# TaaraNodeMini.net
KiCad netlist of a schematic drawn in EAGLE
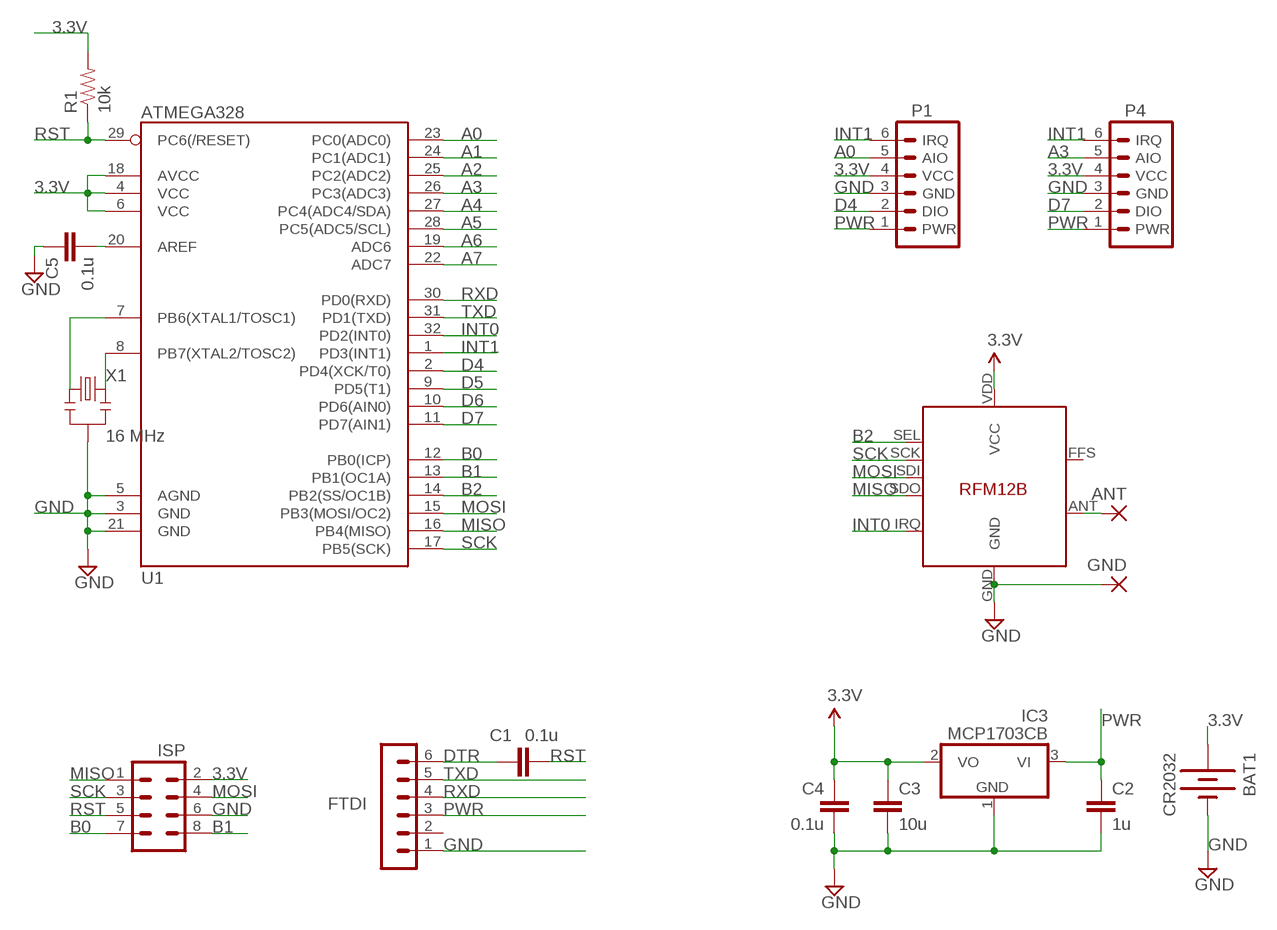
[diagram p0: schematic, sheet 1]

(export (version "E")
  (design (tool "Eeschema 10.0.6"))
  (components
    (comp (ref "ANT")
      (value "1,6/0,8")
      (footprint "eagle-import:1,6_0,8")
      (libsource (lib "eagle-import") (part "1,6/0,8"))
    )
    (comp (ref "BAT1")
      (value "CR2032")
      (footprint "eagle-import:BATTCOM_20MM_PTH")
      (libsource (lib "eagle-import") (part "BATTERY20PTH"))
    )
    (comp (ref "C1")
      (value "0.1u")
      (footprint "eagle-import:0603-CAP")
      (libsource (lib "eagle-import") (part "CAP0603-CAP"))
    )
    (comp (ref "C2")
      (value "1u")
      (footprint "eagle-import:0603-CAP")
      (libsource (lib "eagle-import") (part "CAP0603-CAP"))
    )
    (comp (ref "C3")
      (value "10u")
      (footprint "eagle-import:0805")
      (libsource (lib "eagle-import") (part "CAP0805"))
    )
    (comp (ref "C4")
      (value "0.1u")
      (footprint "eagle-import:0603-CAP")
      (libsource (lib "eagle-import") (part "CAP0603-CAP"))
    )
    (comp (ref "C5")
      (value "0.1u")
      (footprint "eagle-import:0603-CAP")
      (libsource (lib "eagle-import") (part "CAP0603-CAP"))
    )
    (comp (ref "FTDI")
      (value "FTDI")
      (footprint "eagle-import:MA06-1")
      (libsource (lib "eagle-import") (part "MA06-1"))
    )
    (comp (ref "GND")
      (value "1,6/0,8")
      (footprint "eagle-import:1,6_0,8")
      (libsource (lib "eagle-import") (part "1,6/0,8"))
    )
    (comp (ref "IC3")
      (value "MCP1703CB")
      (footprint "eagle-import:SOT23")
      (libsource (lib "eagle-import") (part "MCP1703CB"))
    )
    (comp (ref "P1")
      (value "JEEPORT")
      (footprint "eagle-import:1X06_FEMALE_LOCK.010")
      (libsource (lib "eagle-import") (part "JEEPORT-FEMALE"))
    )
    (comp (ref "P4")
      (value "JEEPORT")
      (footprint "eagle-import:1X06_FEMALE_LOCK.010")
      (libsource (lib "eagle-import") (part "JEEPORT-FEMALE"))
    )
    (comp (ref "R1")
      (value "10k")
      (footprint "eagle-import:0603-RES")
      (libsource (lib "eagle-import") (part "RESISTOR0603-RES"))
    )
    (comp (ref "SV7")
      (value "ISP")
      (footprint "eagle-import:MA04-2")
      (libsource (lib "eagle-import") (part "MA04-2"))
    )
    (comp (ref "U$1")
      (value "RFM12B")
      (footprint "eagle-import:RFM12B")
      (libsource (lib "eagle-import") (part "RFM12B"))
    )
    (comp (ref "U1")
      (value "ATMEGA328")
      (footprint "eagle-import:TQFP32-08")
      (libsource (lib "eagle-import") (part "ATMEGA168"))
    )
    (comp (ref "X1")
      (value "16 MHz")
      (footprint "eagle-import:RESONATOR-SMD")
      (libsource (lib "eagle-import") (part "RESONATORSMD"))
    )
  )
  (nets
    (net (code "1") (name "/A0") (class "Default")
      (node (ref "P1") (pin "5") (pinfunction "AIO_5") (pintype "bidirectional"))
      (node (ref "U1") (pin "23") (pinfunction "PC0(ADC0)_23") (pintype "bidirectional"))
    )
    (net (code "2") (name "/A1") (class "Default")
      (node (ref "U1") (pin "24") (pinfunction "PC1(ADC1)_24") (pintype "bidirectional"))
    )
    (net (code "3") (name "/A2") (class "Default")
      (node (ref "U1") (pin "25") (pinfunction "PC2(ADC2)_25") (pintype "bidirectional"))
    )
    (net (code "4") (name "/A3") (class "Default")
      (node (ref "P4") (pin "5") (pinfunction "AIO_5") (pintype "bidirectional"))
      (node (ref "U1") (pin "26") (pinfunction "PC3(ADC3)_26") (pintype "bidirectional"))
    )
    (net (code "5") (name "/A4") (class "Default")
      (node (ref "U1") (pin "27") (pinfunction "PC4(ADC4/SDA)_27") (pintype "bidirectional"))
    )
    (net (code "6") (name "/A5") (class "Default")
      (node (ref "U1") (pin "28") (pinfunction "PC5(ADC5/SCL)_28") (pintype "bidirectional"))
    )
    (net (code "7") (name "/A6") (class "Default")
      (node (ref "U1") (pin "19") (pinfunction "ADC6_19") (pintype "bidirectional"))
    )
    (net (code "8") (name "/A7") (class "Default")
      (node (ref "U1") (pin "22") (pinfunction "ADC7_22") (pintype "bidirectional"))
    )
    (net (code "9") (name "/B0") (class "Default")
      (node (ref "SV7") (pin "7") (pinfunction "7_7") (pintype "passive"))
      (node (ref "U1") (pin "12") (pinfunction "PB0(ICP)_12") (pintype "bidirectional"))
    )
    (net (code "10") (name "/B1") (class "Default")
      (node (ref "SV7") (pin "8") (pinfunction "8_8") (pintype "passive"))
      (node (ref "U1") (pin "13") (pinfunction "PB1(OC1A)_13") (pintype "bidirectional"))
    )
    (net (code "11") (name "/B2") (class "Default")
      (node (ref "U$1") (pin "SEL") (pinfunction "SEL_SEL") (pintype "input"))
      (node (ref "U1") (pin "14") (pinfunction "PB2(SS/OC1B)_14") (pintype "bidirectional"))
    )
    (net (code "12") (name "/D4") (class "Default")
      (node (ref "P1") (pin "2") (pinfunction "DIO_2") (pintype "bidirectional"))
      (node (ref "U1") (pin "2") (pinfunction "PD4(XCK/T0)_2") (pintype "bidirectional"))
    )
    (net (code "13") (name "/D5") (class "Default")
      (node (ref "U1") (pin "9") (pinfunction "PD5(T1)_9") (pintype "bidirectional"))
    )
    (net (code "14") (name "/D6") (class "Default")
      (node (ref "U1") (pin "10") (pinfunction "PD6(AIN0)_10") (pintype "bidirectional"))
    )
    (net (code "15") (name "/D7") (class "Default")
      (node (ref "P4") (pin "2") (pinfunction "DIO_2") (pintype "bidirectional"))
      (node (ref "U1") (pin "11") (pinfunction "PD7(AIN1)_11") (pintype "bidirectional"))
    )
    (net (code "16") (name "/DTR") (class "Default")
      (node (ref "C1") (pin "2") (pinfunction "2_2") (pintype "passive"))
      (node (ref "FTDI") (pin "6") (pinfunction "6_6") (pintype "passive"))
    )
    (net (code "17") (name "/INT0") (class "Default")
      (node (ref "U$1") (pin "IRQ") (pinfunction "IRQ_IRQ") (pintype "open_collector"))
      (node (ref "U1") (pin "32") (pinfunction "PD2(INT0)_32") (pintype "bidirectional"))
    )
    (net (code "18") (name "/INT1") (class "Default")
      (node (ref "P1") (pin "6") (pinfunction "IRQ_6") (pintype "bidirectional"))
      (node (ref "P4") (pin "6") (pinfunction "IRQ_6") (pintype "bidirectional"))
      (node (ref "U1") (pin "1") (pinfunction "PD3(INT1)_1") (pintype "bidirectional"))
    )
    (net (code "19") (name "/MISO") (class "Default")
      (node (ref "SV7") (pin "1") (pinfunction "1_1") (pintype "passive"))
      (node (ref "U$1") (pin "SDO") (pinfunction "SDO_SDO") (pintype "output"))
      (node (ref "U1") (pin "16") (pinfunction "PB4(MISO)_16") (pintype "bidirectional"))
    )
    (net (code "20") (name "/MOSI") (class "Default")
      (node (ref "SV7") (pin "4") (pinfunction "4_4") (pintype "passive"))
      (node (ref "U$1") (pin "SDI") (pinfunction "SDI_SDI") (pintype "input"))
      (node (ref "U1") (pin "15") (pinfunction "PB3(MOSI/OC2)_15") (pintype "bidirectional"))
    )
    (net (code "21") (name "/PWR") (class "Default")
      (node (ref "C2") (pin "1") (pinfunction "1_1") (pintype "passive"))
      (node (ref "FTDI") (pin "3") (pinfunction "3_3") (pintype "passive"))
      (node (ref "IC3") (pin "3") (pinfunction "VI_3") (pintype "input"))
      (node (ref "P1") (pin "1") (pinfunction "PWR_1") (pintype "power_in"))
      (node (ref "P4") (pin "1") (pinfunction "PWR_1") (pintype "power_in"))
    )
    (net (code "22") (name "/RST") (class "Default")
      (node (ref "C1") (pin "1") (pinfunction "1_1") (pintype "passive"))
      (node (ref "R1") (pin "1") (pinfunction "1_1") (pintype "passive"))
      (node (ref "SV7") (pin "5") (pinfunction "5_5") (pintype "passive"))
      (node (ref "U1") (pin "29") (pinfunction "PC6(/RESET)_29") (pintype "bidirectional"))
    )
    (net (code "23") (name "/RXD") (class "Default")
      (node (ref "FTDI") (pin "4") (pinfunction "4_4") (pintype "passive"))
      (node (ref "U1") (pin "30") (pinfunction "PD0(RXD)_30") (pintype "bidirectional"))
    )
    (net (code "24") (name "/SCK") (class "Default")
      (node (ref "SV7") (pin "3") (pinfunction "3_3") (pintype "passive"))
      (node (ref "U$1") (pin "SCK") (pinfunction "SCK_SCK") (pintype "input"))
      (node (ref "U1") (pin "17") (pinfunction "PB5(SCK)_17") (pintype "bidirectional"))
    )
    (net (code "25") (name "/TXD") (class "Default")
      (node (ref "FTDI") (pin "5") (pinfunction "5_5") (pintype "passive"))
      (node (ref "U1") (pin "31") (pinfunction "PD1(TXD)_31") (pintype "bidirectional"))
    )
    (net (code "26") (name "3.3V") (class "Default")
      (node (ref "BAT1") (pin "1") (pinfunction "+_1") (pintype "power_in"))
      (node (ref "C3") (pin "1") (pinfunction "1_1") (pintype "passive"))
      (node (ref "C4") (pin "1") (pinfunction "1_1") (pintype "passive"))
      (node (ref "IC3") (pin "2") (pinfunction "VO_2") (pintype "passive"))
      (node (ref "P1") (pin "4") (pinfunction "VCC_4") (pintype "power_in"))
      (node (ref "P4") (pin "4") (pinfunction "VCC_4") (pintype "power_in"))
      (node (ref "R1") (pin "2") (pinfunction "2_2") (pintype "passive"))
      (node (ref "SV7") (pin "2") (pinfunction "2_2") (pintype "passive"))
      (node (ref "U$1") (pin "VDD") (pinfunction "VCC_VDD") (pintype "power_in"))
      (node (ref "U1") (pin "18") (pinfunction "AVCC_18") (pintype "bidirectional"))
      (node (ref "U1") (pin "4") (pinfunction "VCC_4") (pintype "bidirectional"))
      (node (ref "U1") (pin "6") (pinfunction "VCC_6") (pintype "bidirectional"))
    )
    (net (code "27") (name "GND") (class "Default")
      (node (ref "BAT1") (pin "2") (pinfunction "-_2") (pintype "power_in"))
      (node (ref "C2") (pin "2") (pinfunction "2_2") (pintype "passive"))
      (node (ref "C3") (pin "2") (pinfunction "2_2") (pintype "passive"))
      (node (ref "C4") (pin "2") (pinfunction "2_2") (pintype "passive"))
      (node (ref "C5") (pin "1") (pinfunction "1_1") (pintype "passive"))
      (node (ref "FTDI") (pin "1") (pinfunction "1_1") (pintype "passive"))
      (node (ref "GND") (pin "1") (pinfunction "P_1") (pintype "passive"))
      (node (ref "IC3") (pin "1") (pinfunction "GND_1") (pintype "passive"))
      (node (ref "P1") (pin "3") (pinfunction "GND_3") (pintype "power_in"))
      (node (ref "P4") (pin "3") (pinfunction "GND_3") (pintype "power_in"))
      (node (ref "SV7") (pin "6") (pinfunction "6_6") (pintype "passive"))
      (node (ref "U$1") (pin "GND") (pinfunction "GND_GND") (pintype "power_in"))
      (node (ref "U1") (pin "21") (pinfunction "GND_21") (pintype "bidirectional"))
      (node (ref "U1") (pin "3") (pinfunction "GND_3") (pintype "bidirectional"))
      (node (ref "U1") (pin "5") (pinfunction "AGND_5") (pintype "bidirectional"))
      (node (ref "X1") (pin "2") (pinfunction "2_2") (pintype "passive"))
    )
    (net (code "28") (name "Net-(ANT-P)") (class "Default")
      (node (ref "ANT") (pin "1") (pinfunction "P_1") (pintype "passive"))
      (node (ref "U$1") (pin "ANT") (pinfunction "ANT_ANT") (pintype "passive"))
    )
    (net (code "29") (name "Net-(U1-AREF)") (class "Default")
      (node (ref "C5") (pin "2") (pinfunction "2_2") (pintype "passive"))
      (node (ref "U1") (pin "20") (pinfunction "AREF_20") (pintype "bidirectional"))
    )
    (net (code "30") (name "Net-(U1-PB6(XTAL1{slash}TOSC1))") (class "Default")
      (node (ref "U1") (pin "7") (pinfunction "PB6(XTAL1/TOSC1)_7") (pintype "bidirectional"))
      (node (ref "X1") (pin "1") (pinfunction "1_1") (pintype "passive"))
    )
    (net (code "31") (name "Net-(U1-PB7(XTAL2{slash}TOSC2))") (class "Default")
      (node (ref "U1") (pin "8") (pinfunction "PB7(XTAL2/TOSC2)_8") (pintype "bidirectional"))
      (node (ref "X1") (pin "3") (pinfunction "3_3") (pintype "passive"))
    )
    (net (code "32") (name "unconnected-(FTDI-Pad2)") (class "Default")
      (node (ref "FTDI") (pin "2") (pinfunction "2_2") (pintype "passive"))
    )
    (net (code "33") (name "unconnected-(U$1-PadFFS)") (class "Default")
      (node (ref "U$1") (pin "FFS") (pinfunction "FFS_FFS") (pintype "bidirectional"))
    )
  )
)
